# FPSController.net
KiCad netlist of a schematic drawn in Altium Designer
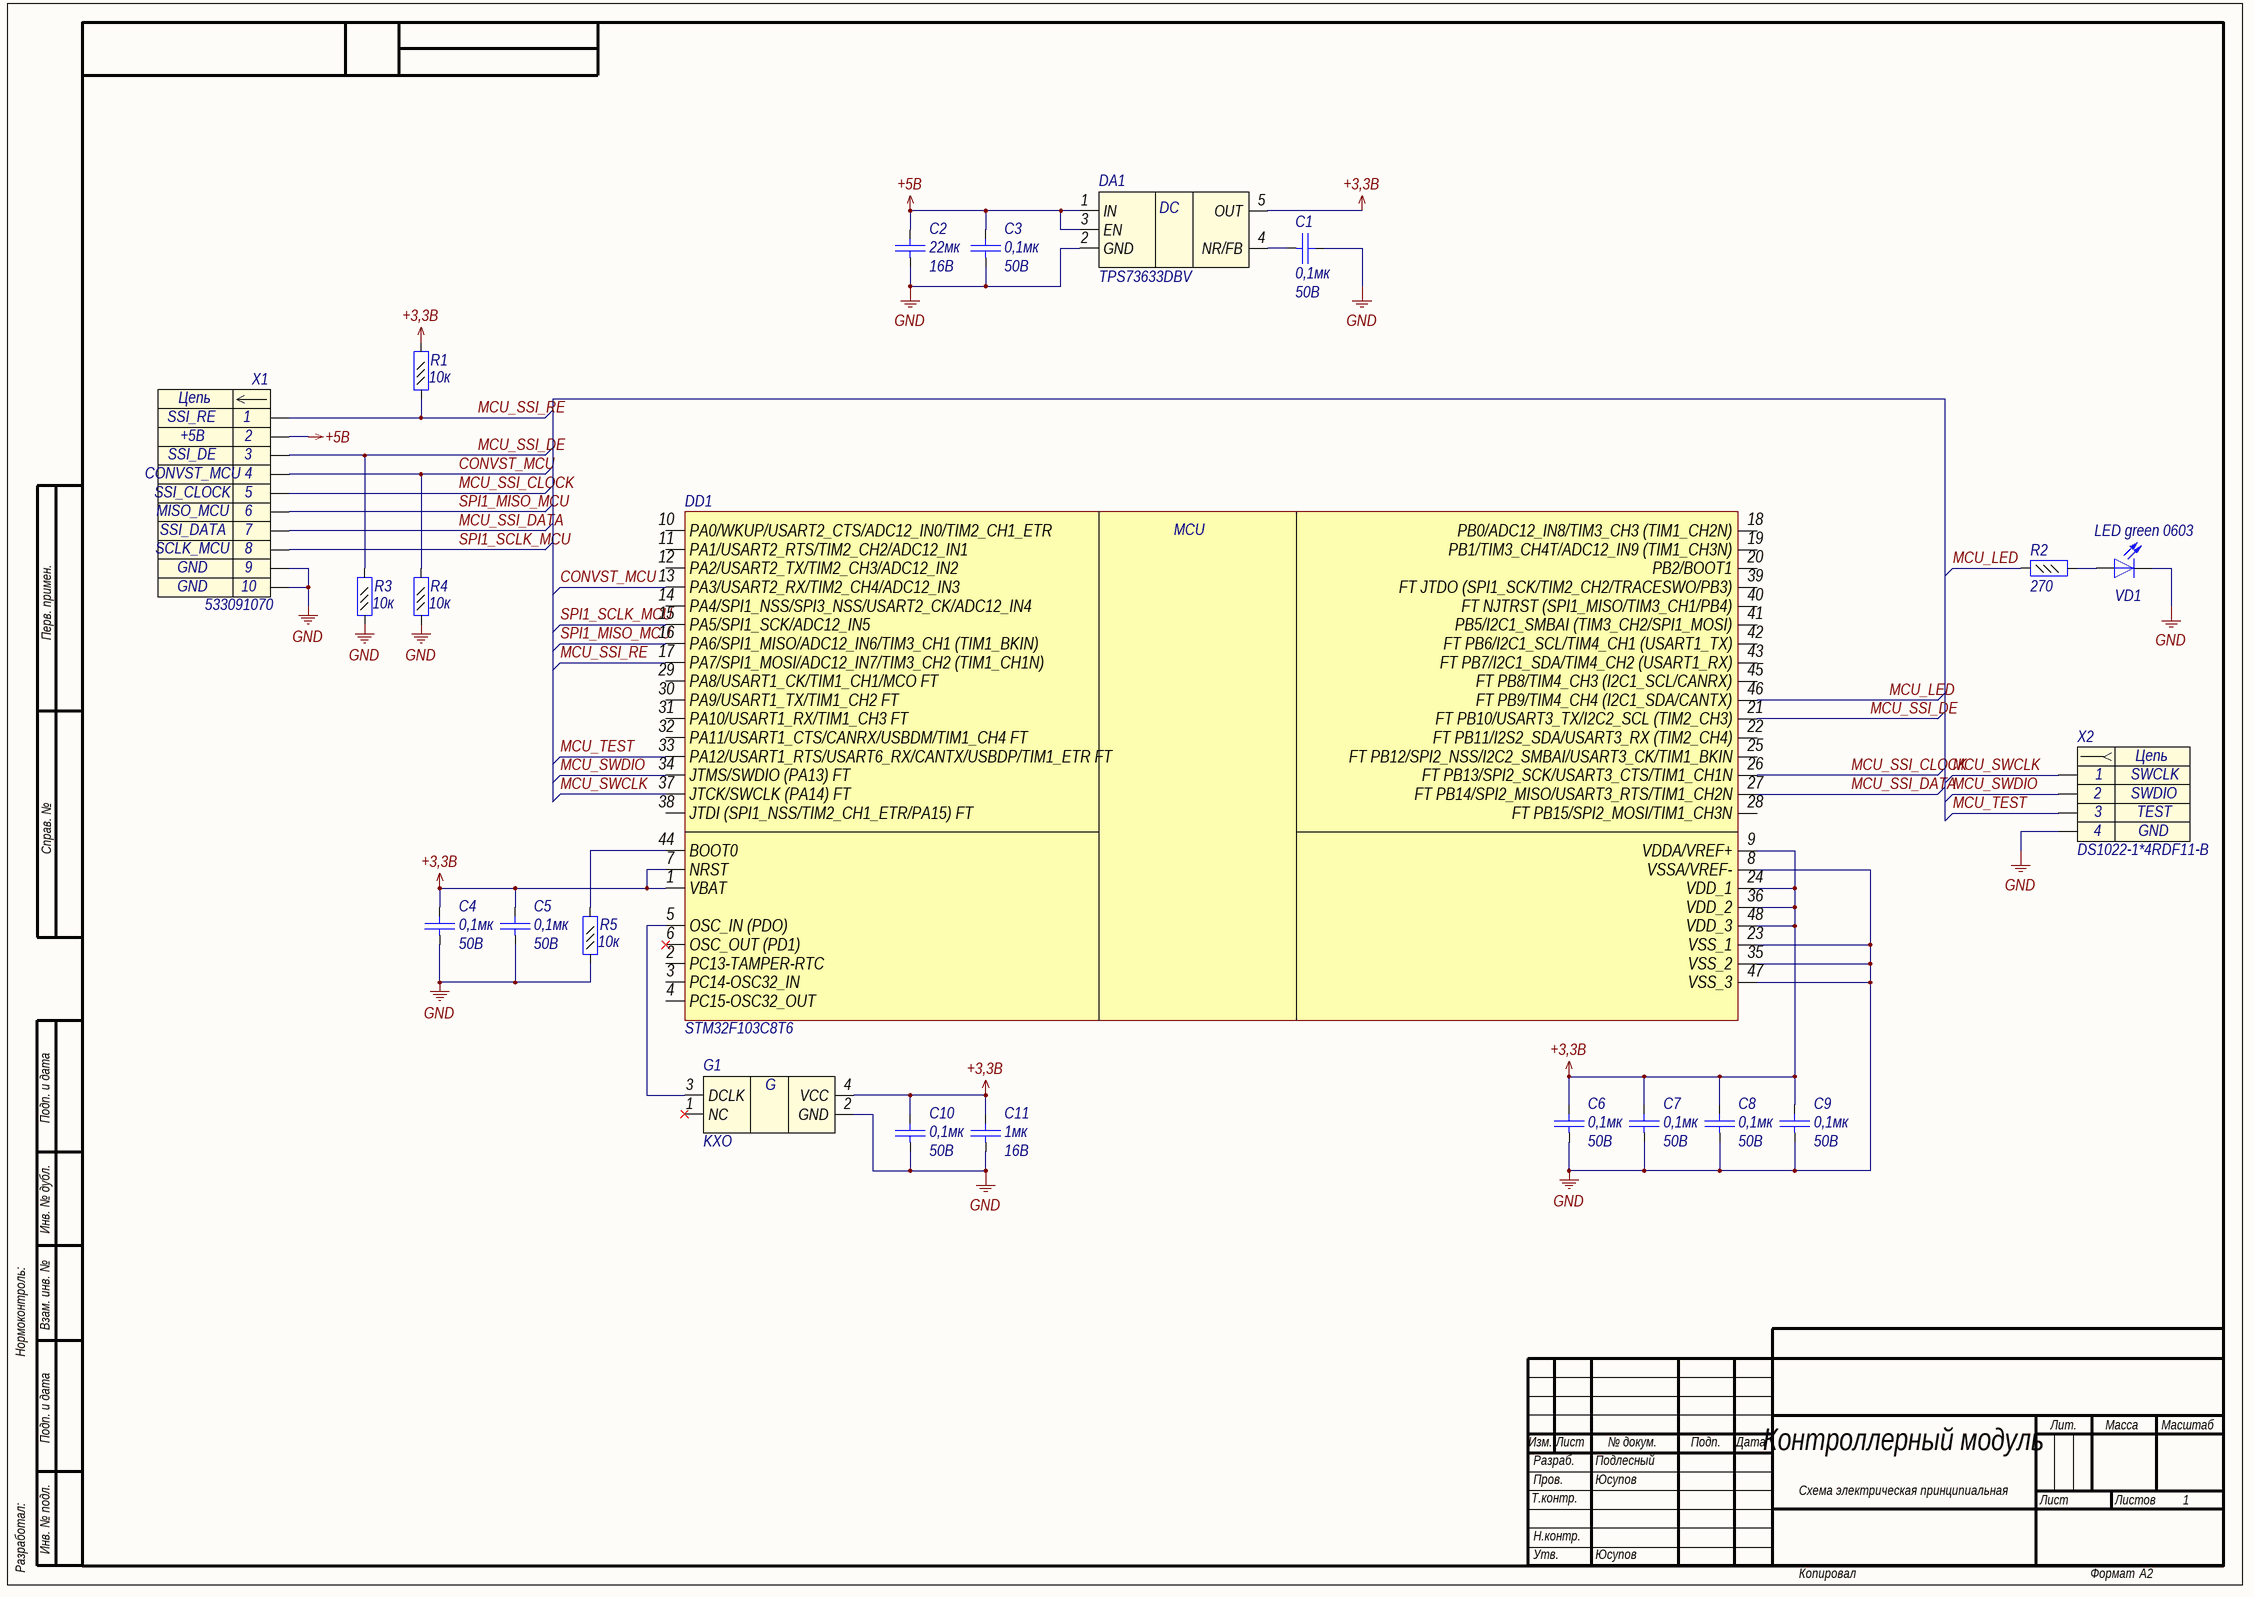
[diagram p0: FPSController.SchDoc]

(export (version "E")
  (design (tool "Eeschema 10.0.6"))
  (components
    (comp (ref "C1")
      (value "0,1мк")
      (footprint "C0402")
      (description "Конденсатор")
      (fields (field (name "VOLTAGE") "50В") (field (name "PART NUMBER") "GRM155R71H104KE14D "))
      (libsource (lib "MOP44") (part "Capacitor"))
    )
    (comp (ref "C2")
      (value "22мк")
      (footprint "C1210")
      (description "Конденсатор")
      (fields (field (name "VOLTAGE") "16B") (field (name "PART NUMBER") "C3225X7R1C226M"))
      (libsource (lib "MOP44") (part "Capacitor"))
    )
    (comp (ref "C3")
      (value "0,1мк")
      (footprint "C0402")
      (description "Конденсатор")
      (fields (field (name "VOLTAGE") "50В") (field (name "PART NUMBER") "GRM155R71H104KE14D "))
      (libsource (lib "MOP44") (part "Capacitor"))
    )
    (comp (ref "C4")
      (value "0,1мк")
      (footprint "C0402")
      (description "Конденсатор")
      (fields (field (name "VOLTAGE") "50В") (field (name "PART NUMBER") "GRM155R71H104KE14D "))
      (libsource (lib "MOP44") (part "Capacitor"))
    )
    (comp (ref "C5")
      (value "0,1мк")
      (footprint "C0402")
      (description "Конденсатор")
      (fields (field (name "VOLTAGE") "50В") (field (name "PART NUMBER") "GRM155R71H104KE14D "))
      (libsource (lib "MOP44") (part "Capacitor"))
    )
    (comp (ref "C6")
      (value "0,1мк")
      (footprint "C0402")
      (description "Конденсатор")
      (fields (field (name "VOLTAGE") "50В") (field (name "PART NUMBER") "GRM155R71H104KE14D "))
      (libsource (lib "MOP44") (part "Capacitor"))
    )
    (comp (ref "C7")
      (value "0,1мк")
      (footprint "C0402")
      (description "Конденсатор")
      (fields (field (name "VOLTAGE") "50В") (field (name "PART NUMBER") "GRM155R71H104KE14D "))
      (libsource (lib "MOP44") (part "Capacitor"))
    )
    (comp (ref "C8")
      (value "0,1мк")
      (footprint "C0402")
      (description "Конденсатор")
      (fields (field (name "VOLTAGE") "50В") (field (name "PART NUMBER") "GRM155R71H104KE14D "))
      (libsource (lib "MOP44") (part "Capacitor"))
    )
    (comp (ref "C9")
      (value "0,1мк")
      (footprint "C0402")
      (description "Конденсатор")
      (fields (field (name "VOLTAGE") "50В") (field (name "PART NUMBER") "GRM155R71H104KE14D "))
      (libsource (lib "MOP44") (part "Capacitor"))
    )
    (comp (ref "C10")
      (value "0,1мк")
      (footprint "C0402")
      (description "Конденсатор")
      (fields
        (field (name "VOLTAGE") "50В")
        (field (name "PART NUMBER") "GRM155R71H104KE14D ")
        (field (name "Comment") "Capacitor")
      )
      (libsource (lib "MOP44") (part "Capacitor"))
    )
    (comp (ref "C11")
      (value "1мк")
      (footprint "C0603")
      (description "Конденсатор")
      (fields
        (field (name "VOLTAGE") "16B")
        (field (name "PART NUMBER") "GRM188R71C105KA12D**")
        (field (name "Comment") "Capacitor")
      )
      (libsource (lib "MOP44") (part "Capacitor"))
    )
    (comp (ref "DA1")
      (value "TPS736DBV")
      (footprint "SOT23-5")
      (description "400-mA Low-Dropout Regulator with Reverse Current  Protection")
      (fields (field (name "PART NUMBER") "TPS73633DBV") (field (name "MANUFACTURER") "Texas Instruments"))
      (libsource (lib "MOP44") (part "TPS736DBV"))
    )
    (comp (ref "DD1")
      (value "STM32F103C8T6")
      (footprint "LQFP48")
      (libsource (lib "MOP44") (part "STM32F103C8T6"))
    )
    (comp (ref "G1")
      (value "KXO")
      (footprint "QSMD7x5.2x1.8")
      (description "Кварц. генер. 32.768 МГц (HCMOS/TTL)")
      (fields (field (name "PART NUMBER") "KXO-V97"))
      (libsource (lib "MOP44") (part "KXO"))
    )
    (comp (ref "R1")
      (value "10к")
      (footprint "R0402")
      (description "Резистор")
      (fields (field (name "PART NUMBER") "RC0402FR-0710KL") (field (name "POWER") "0,062Вт"))
      (libsource (lib "MOP44") (part "Resistor_0,062Вт"))
    )
    (comp (ref "R2")
      (value "270")
      (footprint "R0402")
      (description "Резистор")
      (fields (field (name "PART NUMBER") "RC0402FR-07270RL") (field (name "POWER") "0,062Вт"))
      (libsource (lib "") (part "Resistor_0,062Вт_1"))
    )
    (comp (ref "R3")
      (value "10к")
      (footprint "R0402")
      (description "Резистор")
      (fields (field (name "PART NUMBER") "RC0402FR-0710KL") (field (name "POWER") "0,062Вт"))
      (libsource (lib "MOP44") (part "Resistor_0,062Вт"))
    )
    (comp (ref "R4")
      (value "10к")
      (footprint "R0402")
      (description "Резистор")
      (fields (field (name "PART NUMBER") "RC0402FR-0710KL") (field (name "POWER") "0,062Вт"))
      (libsource (lib "MOP44") (part "Resistor_0,062Вт"))
    )
    (comp (ref "R5")
      (value "10к")
      (footprint "R0402")
      (description "Резистор")
      (fields (field (name "PART NUMBER") "RC0402FR-0710KL") (field (name "POWER") "0,062Вт"))
      (libsource (lib "MOP44") (part "Resistor_0,062Вт"))
    )
    (comp (ref "VD1")
      (value "LED")
      (footprint "L_0603_GREEN")
      (description "Светодиод")
      (fields (field (name "PART NAME") "LED green 0603") (field (name "PART NUMBER") "TO-1608BC-PG"))
      (libsource (lib "MOP44") (part "LED"))
    )
    (comp (ref "X1")
      (value "Header_10_plg")
      (footprint "SlimStack-10pin-angl-plg")
      (description "Разъем - 10 конт. вилка")
      (fields (field (name "PART NUMBER") "533091070"))
      (libsource (lib "MOP44") (part "Header_10_plg"))
    )
    (comp (ref "X2")
      (value "Header_4_sct")
      (footprint "PLS-4R")
      (description "Разъем - 4 конт. розетка")
      (fields (field (name "PART NUMBER") "DS1022-1*4RDF11-B"))
      (libsource (lib "MOP44") (part "Header_4_sct"))
    )
  )
  (nets
    (net (code "1") (name "+3,3B") (class "Default")
      (node (ref "C10") (pin "2") (pinfunction "2_2") (pintype "passive"))
      (node (ref "C11") (pin "2") (pinfunction "2_2") (pintype "passive"))
      (node (ref "C4") (pin "2") (pinfunction "2_2") (pintype "passive"))
      (node (ref "C5") (pin "2") (pinfunction "2_2") (pintype "passive"))
      (node (ref "C6") (pin "2") (pinfunction "2_2") (pintype "passive"))
      (node (ref "C7") (pin "2") (pinfunction "2_2") (pintype "passive"))
      (node (ref "C8") (pin "2") (pinfunction "2_2") (pintype "passive"))
      (node (ref "C9") (pin "2") (pinfunction "2_2") (pintype "passive"))
      (node (ref "DA1") (pin "5") (pinfunction "OUT_5") (pintype "power_in"))
      (node (ref "DD1") (pin "1") (pinfunction "VBAT_1") (pintype "passive"))
      (node (ref "DD1") (pin "24") (pinfunction "VDD_1_24") (pintype "passive"))
      (node (ref "DD1") (pin "36") (pinfunction "VDD_2_36") (pintype "passive"))
      (node (ref "DD1") (pin "48") (pinfunction "VDD_3_48") (pintype "passive"))
      (node (ref "DD1") (pin "7") (pinfunction "NRST_7") (pintype "passive"))
      (node (ref "DD1") (pin "9") (pinfunction "VDDA/VREF+_9") (pintype "passive"))
      (node (ref "G1") (pin "4") (pinfunction "VCC_4") (pintype "power_in"))
      (node (ref "R1") (pin "2") (pinfunction "2_2") (pintype "passive"))
    )
    (net (code "2") (name "+5B") (class "Default")
      (node (ref "C2") (pin "2") (pinfunction "2_2") (pintype "passive"))
      (node (ref "C3") (pin "2") (pinfunction "2_2") (pintype "passive"))
      (node (ref "DA1") (pin "1") (pinfunction "IN_1") (pintype "power_in"))
      (node (ref "DA1") (pin "3") (pinfunction "EN_3") (pintype "power_in"))
      (node (ref "X1") (pin "2") (pinfunction "2_2") (pintype "passive"))
    )
    (net (code "3") (name "/CONVST_MCU") (class "Default")
      (node (ref "DD1") (pin "13") (pinfunction "PA3/USART2_RX/TIM2_CH4/ADC12_IN3_13") (pintype "passive"))
      (node (ref "R4") (pin "2") (pinfunction "2_2") (pintype "passive"))
      (node (ref "X1") (pin "4") (pinfunction "4_4") (pintype "passive"))
    )
    (net (code "4") (name "/MCU_LED") (class "Default")
      (node (ref "DD1") (pin "46") (pinfunction "FT_PB9/TIM4_CH4_(I2C1_SDA/CANTX)_46") (pintype "passive"))
      (node (ref "R2") (pin "1") (pinfunction "1_1") (pintype "passive"))
    )
    (net (code "5") (name "/MCU_SSI_CLOCK") (class "Default")
      (node (ref "DD1") (pin "26") (pinfunction "FT_PB13/SPI2_SCK/USART3_CTS/TIM1_CH1N_26") (pintype "passive"))
      (node (ref "X1") (pin "5") (pinfunction "5_5") (pintype "passive"))
    )
    (net (code "6") (name "/MCU_SSI_DATA") (class "Default")
      (node (ref "DD1") (pin "27") (pinfunction "FT_PB14/SPI2_MISO/USART3_RTS/TIM1_CH2N_27") (pintype "passive"))
      (node (ref "X1") (pin "7") (pinfunction "7_7") (pintype "passive"))
    )
    (net (code "7") (name "/MCU_SSI_DE") (class "Default")
      (node (ref "DD1") (pin "21") (pinfunction "FT_PB10/USART3_TX/I2C2_SCL_(TIM2_CH3)_21") (pintype "passive"))
      (node (ref "R3") (pin "2") (pinfunction "2_2") (pintype "passive"))
      (node (ref "X1") (pin "3") (pinfunction "3_3") (pintype "passive"))
    )
    (net (code "8") (name "/MCU_SSI_RE") (class "Default")
      (node (ref "DD1") (pin "17") (pinfunction "PA7/SPI1_MOSI/ADC12_IN7/TIM3_CH2_(TIM1_CH1N)_17") (pintype "passive"))
      (node (ref "R1") (pin "1") (pinfunction "1_1") (pintype "passive"))
      (node (ref "X1") (pin "1") (pinfunction "1_1") (pintype "passive"))
    )
    (net (code "9") (name "/MCU_SWCLK") (class "Default")
      (node (ref "DD1") (pin "37") (pinfunction "JTCK/SWCLK_(PA14)_FT_37") (pintype "passive"))
      (node (ref "X2") (pin "1") (pinfunction "1_1") (pintype "passive"))
    )
    (net (code "10") (name "/MCU_SWDIO") (class "Default")
      (node (ref "DD1") (pin "34") (pinfunction "JTMS/SWDIO_(PA13)_FT_34") (pintype "passive"))
      (node (ref "X2") (pin "2") (pinfunction "2_2") (pintype "passive"))
    )
    (net (code "11") (name "/MCU_TEST") (class "Default")
      (node (ref "DD1") (pin "33") (pinfunction "PA12/USART1_RTS/USART6_RX/CANTX/USBDP/TIM1_ETR_FT_33") (pintype "passive"))
      (node (ref "X2") (pin "3") (pinfunction "3_3") (pintype "passive"))
    )
    (net (code "12") (name "/SPI1_MISO_MCU") (class "Default")
      (node (ref "DD1") (pin "16") (pinfunction "PA6/SPI1_MISO/ADC12_IN6/TIM3_CH1_(TIM1_BKIN)_16") (pintype "passive"))
      (node (ref "X1") (pin "6") (pinfunction "6_6") (pintype "passive"))
    )
    (net (code "13") (name "/SPI1_SCLK_MCU") (class "Default")
      (node (ref "DD1") (pin "15") (pinfunction "PA5/SPI1_SCK/ADC12_IN5_15") (pintype "passive"))
      (node (ref "X1") (pin "8") (pinfunction "8_8") (pintype "passive"))
    )
    (net (code "14") (name "GND") (class "Default")
      (node (ref "C1") (pin "2") (pinfunction "2_2") (pintype "passive"))
      (node (ref "C10") (pin "1") (pinfunction "1_1") (pintype "passive"))
      (node (ref "C11") (pin "1") (pinfunction "1_1") (pintype "passive"))
      (node (ref "C2") (pin "1") (pinfunction "1_1") (pintype "passive"))
      (node (ref "C3") (pin "1") (pinfunction "1_1") (pintype "passive"))
      (node (ref "C4") (pin "1") (pinfunction "1_1") (pintype "passive"))
      (node (ref "C5") (pin "1") (pinfunction "1_1") (pintype "passive"))
      (node (ref "C6") (pin "1") (pinfunction "1_1") (pintype "passive"))
      (node (ref "C7") (pin "1") (pinfunction "1_1") (pintype "passive"))
      (node (ref "C8") (pin "1") (pinfunction "1_1") (pintype "passive"))
      (node (ref "C9") (pin "1") (pinfunction "1_1") (pintype "passive"))
      (node (ref "DA1") (pin "2") (pinfunction "GND_2") (pintype "power_in"))
      (node (ref "DD1") (pin "23") (pinfunction "VSS_1_23") (pintype "passive"))
      (node (ref "DD1") (pin "35") (pinfunction "VSS_2_35") (pintype "passive"))
      (node (ref "DD1") (pin "47") (pinfunction "VSS_3_47") (pintype "passive"))
      (node (ref "DD1") (pin "8") (pinfunction "VSSA/VREF-_8") (pintype "passive"))
      (node (ref "G1") (pin "2") (pinfunction "GND_2") (pintype "power_in"))
      (node (ref "R3") (pin "1") (pinfunction "1_1") (pintype "passive"))
      (node (ref "R4") (pin "1") (pinfunction "1_1") (pintype "passive"))
      (node (ref "R5") (pin "1") (pinfunction "1_1") (pintype "passive"))
      (node (ref "VD1") (pin "1") (pinfunction "K_1") (pintype "passive"))
      (node (ref "X1") (pin "10") (pinfunction "10_10") (pintype "passive"))
      (node (ref "X1") (pin "9") (pinfunction "9_9") (pintype "passive"))
      (node (ref "X2") (pin "4") (pinfunction "4_4") (pintype "passive"))
    )
    (net (code "15") (name "Net-(DA1-NR{slash}FB)") (class "Default")
      (node (ref "C1") (pin "1") (pinfunction "1_1") (pintype "passive"))
      (node (ref "DA1") (pin "4") (pinfunction "NR/FB_4") (pintype "power_in"))
    )
    (net (code "16") (name "Net-(DD1-BOOT0)") (class "Default")
      (node (ref "DD1") (pin "44") (pinfunction "BOOT0_44") (pintype "passive"))
      (node (ref "R5") (pin "2") (pinfunction "2_2") (pintype "passive"))
    )
    (net (code "17") (name "Net-(DD1-OSC_IN_(PDO))") (class "Default")
      (node (ref "DD1") (pin "5") (pinfunction "OSC_IN_(PDO)_5") (pintype "passive"))
      (node (ref "G1") (pin "3") (pinfunction "DCLK_3") (pintype "power_in"))
    )
    (net (code "18") (name "Net-(VD1-A)") (class "Default")
      (node (ref "R2") (pin "2") (pinfunction "2_2") (pintype "passive"))
      (node (ref "VD1") (pin "2") (pinfunction "A_2") (pintype "passive"))
    )
    (net (code "19") (name "unconnected-(DD1-FT_JTDO_(SPI1_SCK{slash}TIM2_CH2{slash}TRACESWO{slash}PB3)-Pad39)") (class "Default")
      (node (ref "DD1") (pin "39") (pinfunction "FT_JTDO_(SPI1_SCK/TIM2_CH2/TRACESWO/PB3)_39") (pintype "passive"))
    )
    (net (code "20") (name "unconnected-(DD1-FT_NJTRST_(SPI1_MISO{slash}TIM3_CH1{slash}PB4)-Pad40)") (class "Default")
      (node (ref "DD1") (pin "40") (pinfunction "FT_NJTRST_(SPI1_MISO/TIM3_CH1/PB4)_40") (pintype "passive"))
    )
    (net (code "21") (name "unconnected-(DD1-FT_PB6{slash}I2C1_SCL{slash}TIM4_CH1_(USART1_TX)-Pad42)") (class "Default")
      (node (ref "DD1") (pin "42") (pinfunction "FT_PB6/I2C1_SCL/TIM4_CH1_(USART1_TX)_42") (pintype "passive"))
    )
    (net (code "22") (name "unconnected-(DD1-FT_PB7{slash}I2C1_SDA{slash}TIM4_CH2_(USART1_RX)-Pad43)") (class "Default")
      (node (ref "DD1") (pin "43") (pinfunction "FT_PB7/I2C1_SDA/TIM4_CH2_(USART1_RX)_43") (pintype "passive"))
    )
    (net (code "23") (name "unconnected-(DD1-FT_PB8{slash}TIM4_CH3_(I2C1_SCL{slash}CANRX)-Pad45)") (class "Default")
      (node (ref "DD1") (pin "45") (pinfunction "FT_PB8/TIM4_CH3_(I2C1_SCL/CANRX)_45") (pintype "passive"))
    )
    (net (code "24") (name "unconnected-(DD1-FT_PB11{slash}I2S2_SDA{slash}USART3_RX_(TIM2_CH4)-Pad22)") (class "Default")
      (node (ref "DD1") (pin "22") (pinfunction "FT_PB11/I2S2_SDA/USART3_RX_(TIM2_CH4)_22") (pintype "passive"))
    )
    (net (code "25") (name "unconnected-(DD1-FT_PB12{slash}SPI2_NSS{slash}I2C2_SMBAI{slash}USART3_CK{slash}TIM1_BKIN-Pad25)") (class "Default")
      (node (ref "DD1") (pin "25") (pinfunction "FT_PB12/SPI2_NSS/I2C2_SMBAI/USART3_CK/TIM1_BKIN_25") (pintype "passive"))
    )
    (net (code "26") (name "unconnected-(DD1-FT_PB15{slash}SPI2_MOSI{slash}TIM1_CH3N-Pad28)") (class "Default")
      (node (ref "DD1") (pin "28") (pinfunction "FT_PB15/SPI2_MOSI/TIM1_CH3N_28") (pintype "passive"))
    )
    (net (code "27") (name "unconnected-(DD1-JTDI_(SPI1_NSS{slash}TIM2_CH1_ETR{slash}PA15)_FT-Pad38)") (class "Default")
      (node (ref "DD1") (pin "38") (pinfunction "JTDI_(SPI1_NSS/TIM2_CH1_ETR/PA15)_FT_38") (pintype "passive"))
    )
    (net (code "28") (name "unconnected-(DD1-OSC_OUT_(PD1)-Pad6)") (class "Default")
      (node (ref "DD1") (pin "6") (pinfunction "OSC_OUT_(PD1)_6") (pintype "passive+no_connect"))
    )
    (net (code "29") (name "unconnected-(DD1-PA0{slash}WKUP{slash}USART2_CTS{slash}ADC12_IN0{slash}TIM2_CH1_ETR-Pad10)") (class "Default")
      (node (ref "DD1") (pin "10") (pinfunction "PA0/WKUP/USART2_CTS/ADC12_IN0/TIM2_CH1_ETR_10") (pintype "passive"))
    )
    (net (code "30") (name "unconnected-(DD1-PA1{slash}USART2_RTS{slash}TIM2_CH2{slash}ADC12_IN1-Pad11)") (class "Default")
      (node (ref "DD1") (pin "11") (pinfunction "PA1/USART2_RTS/TIM2_CH2/ADC12_IN1_11") (pintype "passive"))
    )
    (net (code "31") (name "unconnected-(DD1-PA2{slash}USART2_TX{slash}TIM2_CH3{slash}ADC12_IN2-Pad12)") (class "Default")
      (node (ref "DD1") (pin "12") (pinfunction "PA2/USART2_TX/TIM2_CH3/ADC12_IN2_12") (pintype "passive"))
    )
    (net (code "32") (name "unconnected-(DD1-PA4{slash}SPI1_NSS{slash}SPI3_NSS{slash}USART2_CK{slash}ADC12_IN4-Pad14)") (class "Default")
      (node (ref "DD1") (pin "14") (pinfunction "PA4/SPI1_NSS/SPI3_NSS/USART2_CK/ADC12_IN4_14") (pintype "passive"))
    )
    (net (code "33") (name "unconnected-(DD1-PA8{slash}USART1_CK{slash}TIM1_CH1{slash}MCO_FT-Pad29)") (class "Default")
      (node (ref "DD1") (pin "29") (pinfunction "PA8/USART1_CK/TIM1_CH1/MCO_FT_29") (pintype "passive"))
    )
    (net (code "34") (name "unconnected-(DD1-PA9{slash}USART1_TX{slash}TIM1_CH2_FT-Pad30)") (class "Default")
      (node (ref "DD1") (pin "30") (pinfunction "PA9/USART1_TX/TIM1_CH2_FT_30") (pintype "passive"))
    )
    (net (code "35") (name "unconnected-(DD1-PA10{slash}USART1_RX{slash}TIM1_CH3_FT-Pad31)") (class "Default")
      (node (ref "DD1") (pin "31") (pinfunction "PA10/USART1_RX/TIM1_CH3_FT_31") (pintype "passive"))
    )
    (net (code "36") (name "unconnected-(DD1-PA11{slash}USART1_CTS{slash}CANRX{slash}USBDM{slash}TIM1_CH4_FT-Pad32)") (class "Default")
      (node (ref "DD1") (pin "32") (pinfunction "PA11/USART1_CTS/CANRX/USBDM/TIM1_CH4_FT_32") (pintype "passive"))
    )
    (net (code "37") (name "unconnected-(DD1-PB0{slash}ADC12_IN8{slash}TIM3_CH3_(TIM1_CH2N)-Pad18)") (class "Default")
      (node (ref "DD1") (pin "18") (pinfunction "PB0/ADC12_IN8/TIM3_CH3_(TIM1_CH2N)_18") (pintype "passive"))
    )
    (net (code "38") (name "unconnected-(DD1-PB1{slash}TIM3_CH4T{slash}ADC12_IN9_(TIM1_CH3N)-Pad19)") (class "Default")
      (node (ref "DD1") (pin "19") (pinfunction "PB1/TIM3_CH4T/ADC12_IN9_(TIM1_CH3N)_19") (pintype "passive"))
    )
    (net (code "39") (name "unconnected-(DD1-PB2{slash}BOOT1-Pad20)") (class "Default")
      (node (ref "DD1") (pin "20") (pinfunction "PB2/BOOT1_20") (pintype "passive"))
    )
    (net (code "40") (name "unconnected-(DD1-PB5{slash}I2C1_SMBAI_(TIM3_CH2{slash}SPI1_MOSI)-Pad41)") (class "Default")
      (node (ref "DD1") (pin "41") (pinfunction "PB5/I2C1_SMBAI_(TIM3_CH2/SPI1_MOSI)_41") (pintype "passive"))
    )
    (net (code "41") (name "unconnected-(DD1-PC13-TAMPER-RTC-Pad2)") (class "Default")
      (node (ref "DD1") (pin "2") (pinfunction "PC13-TAMPER-RTC_2") (pintype "passive"))
    )
    (net (code "42") (name "unconnected-(DD1-PC14-OSC32_IN-Pad3)") (class "Default")
      (node (ref "DD1") (pin "3") (pinfunction "PC14-OSC32_IN_3") (pintype "passive"))
    )
    (net (code "43") (name "unconnected-(DD1-PC15-OSC32_OUT-Pad4)") (class "Default")
      (node (ref "DD1") (pin "4") (pinfunction "PC15-OSC32_OUT_4") (pintype "passive"))
    )
    (net (code "44") (name "unconnected-(G1-NC-Pad1)") (class "Default")
      (node (ref "G1") (pin "1") (pinfunction "NC_1") (pintype "power_in+no_connect"))
    )
  )
)
